# PDB2_1.net
KiCad netlist of a schematic drawn in EAGLE
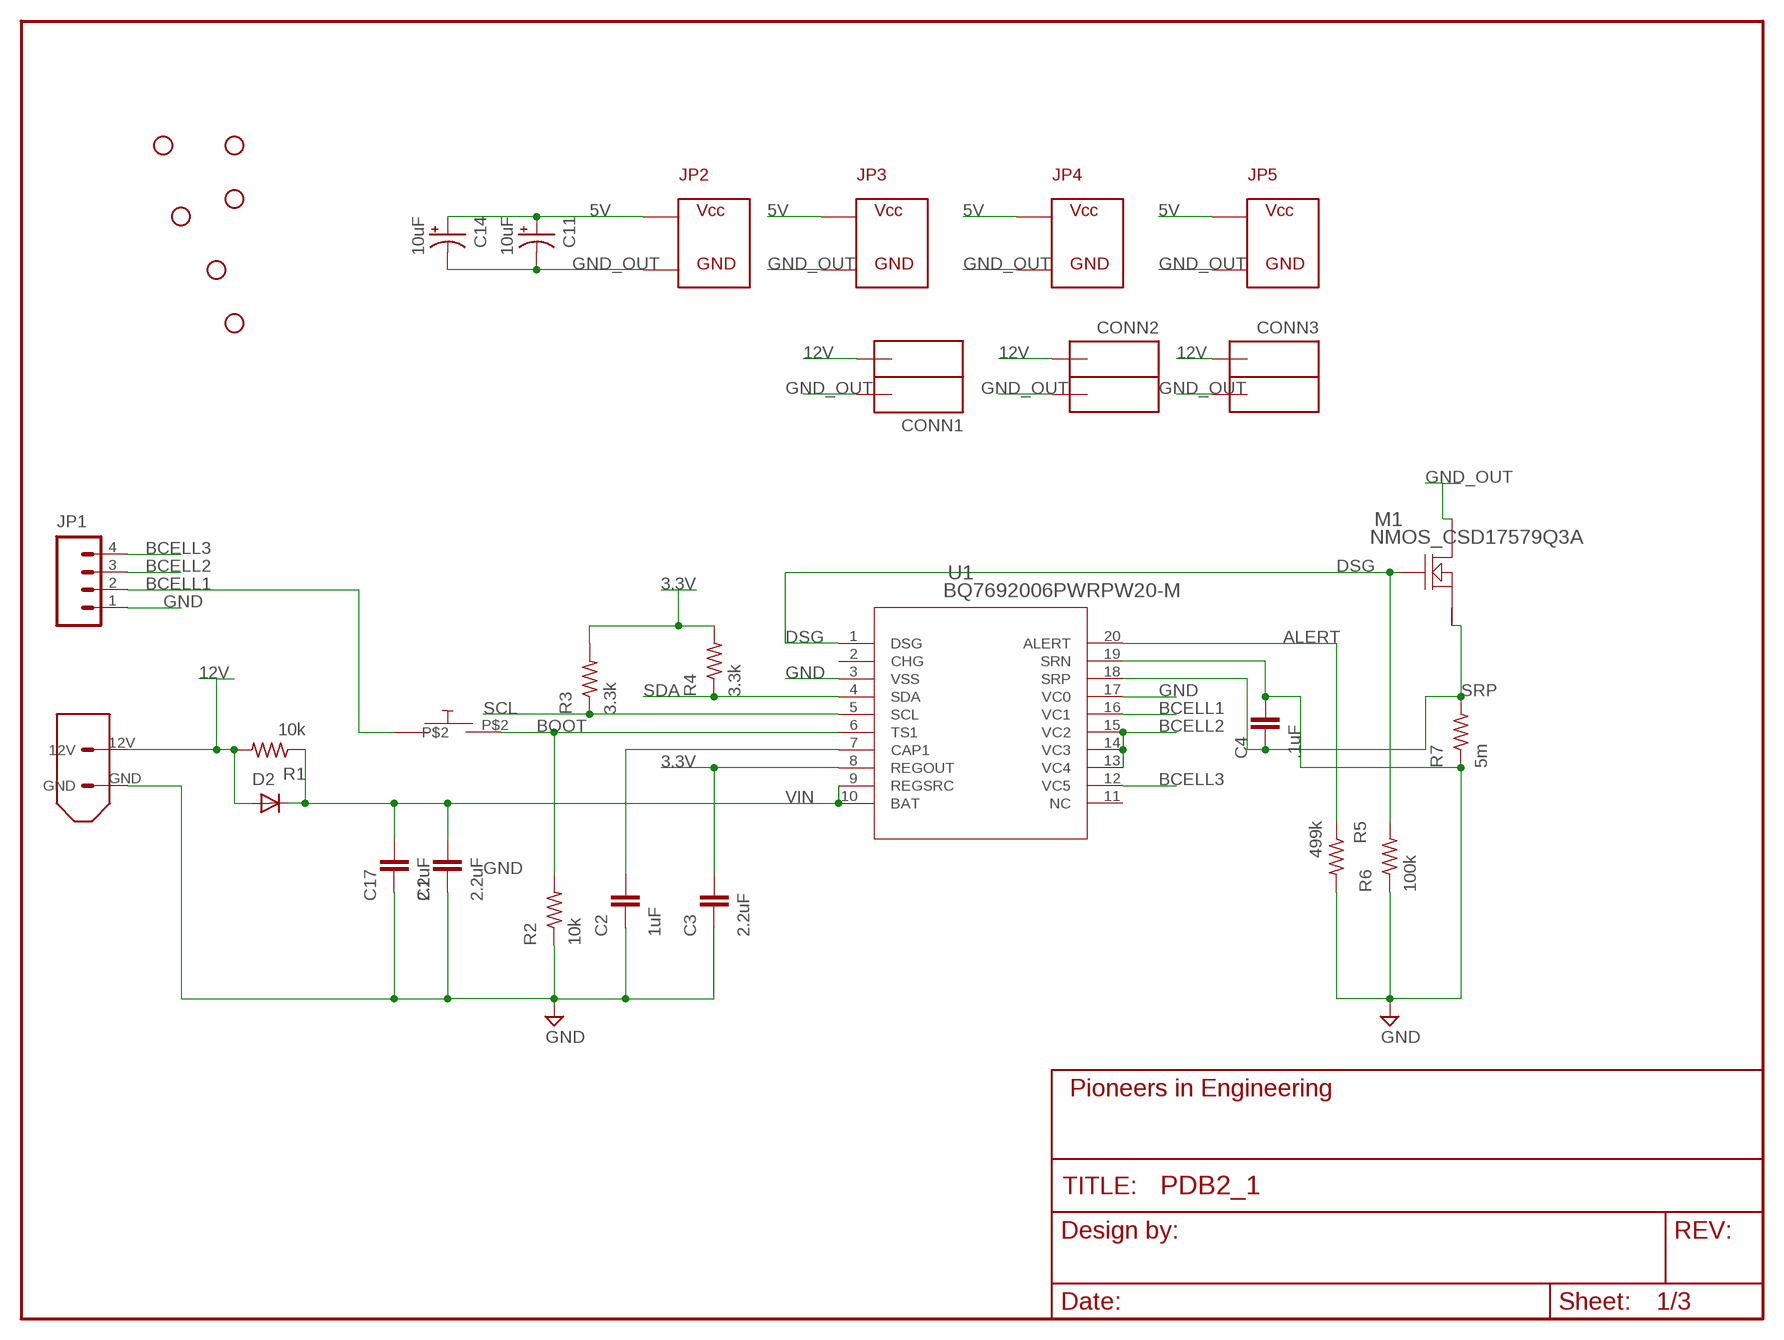
[diagram p0: schematic, sheet 1]
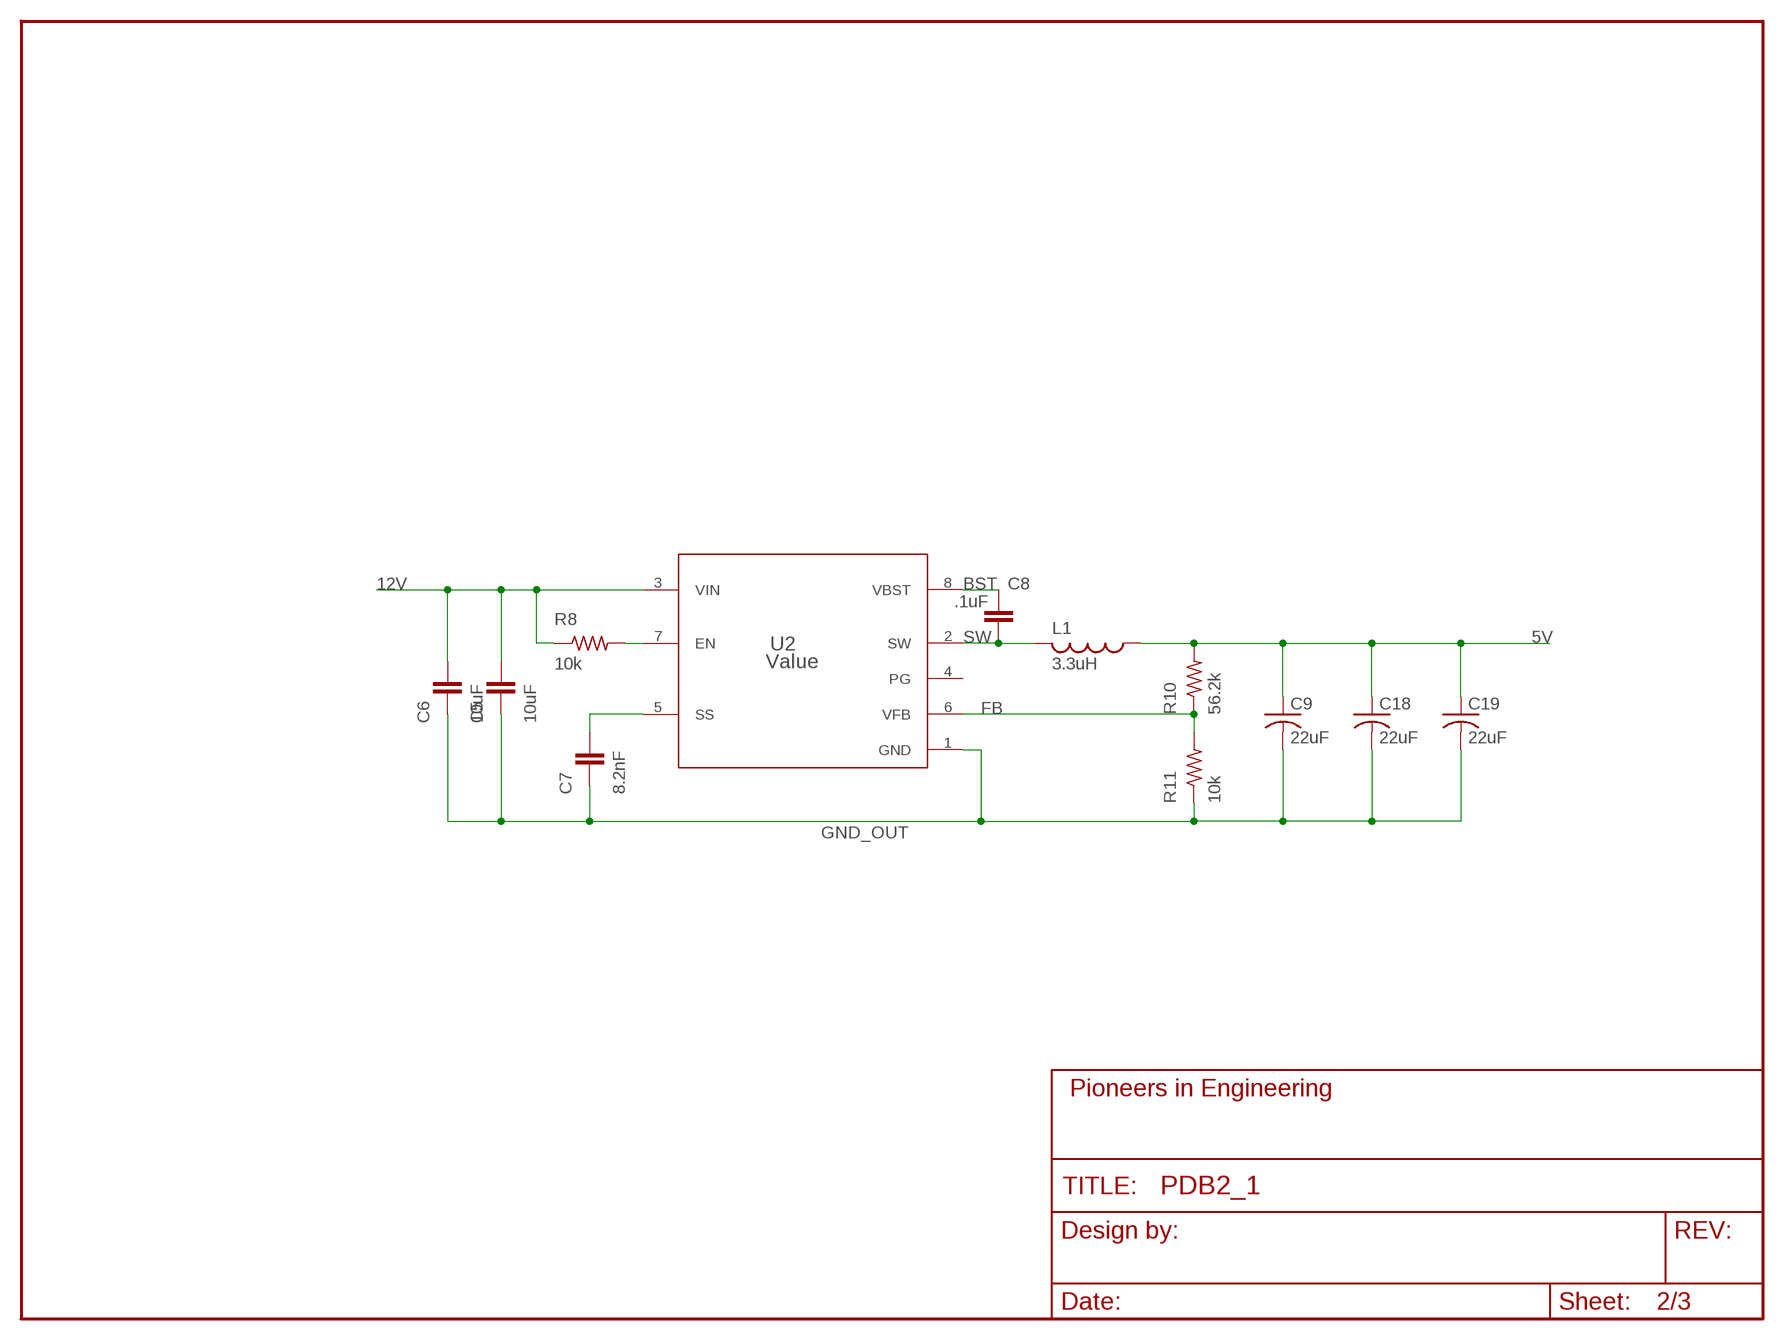
[diagram p1: schematic, sheet 2]
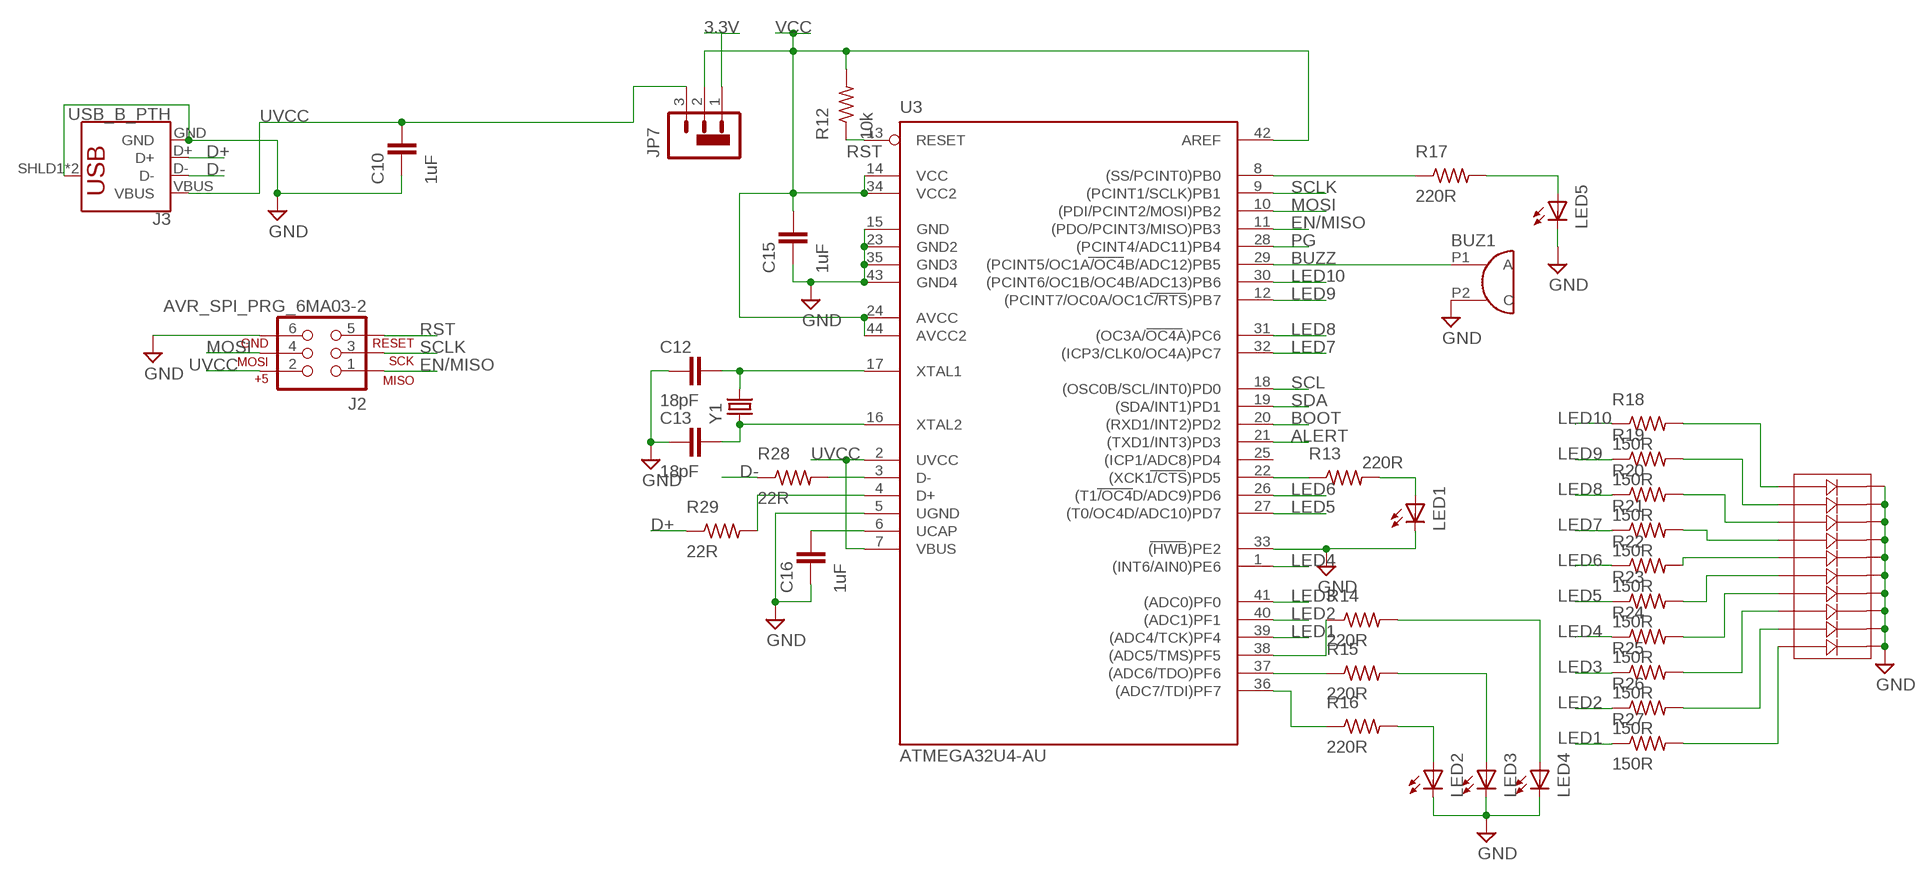
[diagram p2: schematic, sheet 3]

(export (version "E")
  (design (tool "Eeschema 10.0.6"))
  (components
    (comp (ref "C1")
      (value "2.2uF")
      (footprint "eagle-import:0603-CAP")
      (libsource (lib "eagle-import") (part "CAP0603-CAP"))
    )
    (comp (ref "C2")
      (value "1uF")
      (footprint "eagle-import:0603-CAP")
      (libsource (lib "eagle-import") (part "CAP0603-CAP"))
    )
    (comp (ref "C3")
      (value "2.2uF")
      (footprint "eagle-import:0603-CAP")
      (libsource (lib "eagle-import") (part "CAP0603-CAP"))
    )
    (comp (ref "C4")
      (value ".1uF")
      (footprint "eagle-import:0603-CAP")
      (libsource (lib "eagle-import") (part "CAP0603-CAP"))
    )
    (comp (ref "C11")
      (value "10uF")
      (footprint "eagle-import:.248_CAP_THRU")
      (libsource (lib "eagle-import") (part "CAP_POLRADIAL"))
    )
    (comp (ref "C14")
      (value "10uF")
      (footprint "eagle-import:.248_CAP_THRU")
      (libsource (lib "eagle-import") (part "CAP_POLRADIAL"))
    )
    (comp (ref "C17")
      (value "2.2uF")
      (footprint "eagle-import:0603-CAP")
      (libsource (lib "eagle-import") (part "CAP0603-CAP"))
    )
    (comp (ref "CONN1")
      (value "ANDERSONVERTICAL")
      (footprint "eagle-import:ANDERSON_VERTICAL")
      (libsource (lib "eagle-import") (part "ANDERSONVERTICAL"))
    )
    (comp (ref "CONN2")
      (value "ANDERSONVERTICAL")
      (footprint "eagle-import:ANDERSON_VERTICAL")
      (libsource (lib "eagle-import") (part "ANDERSONVERTICAL"))
    )
    (comp (ref "CONN3")
      (value "ANDERSONVERTICAL")
      (footprint "eagle-import:ANDERSON_VERTICAL")
      (libsource (lib "eagle-import") (part "ANDERSONVERTICAL"))
    )
    (comp (ref "D2")
      (value "D_MBR1020VL")
      (footprint "eagle-import:SOD-123FL")
      (fields (field (name "PART_NO") "MBR1020VL"))
      (libsource (lib "eagle-import") (part "D_MBR1020VL"))
    )
    (comp (ref "J1")
      (value "XT60CONNECTOR")
      (footprint "eagle-import:XT60CONNECTOR")
      (fields (field (name "PARTNUMBER") "PRT-10474 "))
      (libsource (lib "eagle-import") (part "XT60CONNECTOR"))
    )
    (comp (ref "JP1")
      (value "M041X04-MTA")
      (footprint "eagle-import:1X04-MTA")
      (libsource (lib "eagle-import") (part "M041X04-MTA"))
    )
    (comp (ref "JP2")
      (value "ATX")
      (footprint "eagle-import:ATX")
      (libsource (lib "eagle-import") (part "ATX"))
    )
    (comp (ref "JP3")
      (value "ATX")
      (footprint "eagle-import:ATX")
      (libsource (lib "eagle-import") (part "ATX"))
    )
    (comp (ref "JP4")
      (value "ATX")
      (footprint "eagle-import:ATX")
      (libsource (lib "eagle-import") (part "ATX"))
    )
    (comp (ref "JP5")
      (value "ATX")
      (footprint "eagle-import:ATX")
      (libsource (lib "eagle-import") (part "ATX"))
    )
    (comp (ref "M1")
      (value "NMOS_CSD17579Q3A")
      (footprint "eagle-import:DNH0008A")
      (fields
        (field (name "MANUFACTURER_PART_NUMBER") "CSD17579Q3A")
        (field (name "MANUFACTURER_PART_NUMBER_1") "CSD16401Q5")
      )
      (libsource (lib "eagle-import") (part "NMOS_CSD17579Q3A"))
    )
    (comp (ref "R1")
      (value "10k")
      (footprint "eagle-import:R0603")
      (fields (field (name "MANUFACTURER") "Rohm Semiconductor"))
      (libsource (lib "eagle-import") (part "R-US_R0603"))
    )
    (comp (ref "R2")
      (value "10k")
      (footprint "eagle-import:R0603")
      (fields (field (name "MANUFACTURER") "Rohm Semiconductor"))
      (libsource (lib "eagle-import") (part "R-US_R0603"))
    )
    (comp (ref "R3")
      (value "3.3k")
      (footprint "eagle-import:R0603")
      (fields (field (name "MANUFACTURER") "Rohm Semiconductor"))
      (libsource (lib "eagle-import") (part "R-US_R0603"))
    )
    (comp (ref "R4")
      (value "3.3k")
      (footprint "eagle-import:R0603")
      (fields (field (name "MANUFACTURER") "Rohm Semiconductor"))
      (libsource (lib "eagle-import") (part "R-US_R0603"))
    )
    (comp (ref "R5")
      (value "499k")
      (footprint "eagle-import:R0603")
      (fields (field (name "MANUFACTURER") "Rohm Semiconductor"))
      (libsource (lib "eagle-import") (part "R-US_R0603"))
    )
    (comp (ref "R6")
      (value "100k")
      (footprint "eagle-import:R0603")
      (fields (field (name "MANUFACTURER") "Rohm Semiconductor"))
      (libsource (lib "eagle-import") (part "R-US_R0603"))
    )
    (comp (ref "R7")
      (value "5m")
      (footprint "eagle-import:SMD_SHUNT")
      (fields (field (name "MANUFACTURER_PART_NO") "WSHM28185L000FEA"))
      (libsource (lib "eagle-import") (part "SHUNT_SMD"))
    )
    (comp (ref "STANDOFF1")
      (value "STAND-OFFTIGHT")
      (footprint "eagle-import:STAND-OFF-TIGHT")
      (libsource (lib "eagle-import") (part "STAND-OFFTIGHT"))
    )
    (comp (ref "STANDOFF2")
      (value "STAND-OFFTIGHT")
      (footprint "eagle-import:STAND-OFF-TIGHT")
      (libsource (lib "eagle-import") (part "STAND-OFFTIGHT"))
    )
    (comp (ref "STANDOFF3")
      (value "STAND-OFFTIGHT")
      (footprint "eagle-import:STAND-OFF-TIGHT")
      (libsource (lib "eagle-import") (part "STAND-OFFTIGHT"))
    )
    (comp (ref "STANDOFF4")
      (value "STAND-OFFTIGHT")
      (footprint "eagle-import:STAND-OFF-TIGHT")
      (libsource (lib "eagle-import") (part "STAND-OFFTIGHT"))
    )
    (comp (ref "STANDOFF5")
      (value "STAND-OFFTIGHT")
      (footprint "eagle-import:STAND-OFF-TIGHT")
      (libsource (lib "eagle-import") (part "STAND-OFFTIGHT"))
    )
    (comp (ref "STANDOFF7")
      (value "STAND-OFFTIGHT")
      (footprint "eagle-import:STAND-OFF-TIGHT")
      (libsource (lib "eagle-import") (part "STAND-OFFTIGHT"))
    )
    (comp (ref "SW1")
      (value "PUSH_BUTTON")
      (footprint "eagle-import:BUTTON_K12A")
      (libsource (lib "eagle-import") (part "PUSH_BUTTON"))
    )
    (comp (ref "U1")
      (value "BQ7692006PWRPW20-M")
      (footprint "eagle-import:PW20-M")
      (fields (field (name "MANUFACTURER_PART_NUMBER") "BQ7692006PWR"))
      (libsource (lib "eagle-import") (part "BQ7692006PWRPW20-M"))
    )
    (comp (ref "BUZ1")
      (value "BUZZER3.3VBUZZER")
      (footprint "eagle-import:BUZZER_3.3V")
      (libsource (lib "eagle-import") (part "BUZZER3.3VBUZZER"))
    )
    (comp (ref "C10")
      (value "1uF")
      (footprint "eagle-import:0603-CAP")
      (libsource (lib "eagle-import") (part "CAP0603-CAP"))
    )
    (comp (ref "C12")
      (value "18pF")
      (footprint "eagle-import:0603-CAP")
      (libsource (lib "eagle-import") (part "CAP0603-CAP"))
    )
    (comp (ref "C13")
      (value "18pF")
      (footprint "eagle-import:0603-CAP")
      (libsource (lib "eagle-import") (part "CAP0603-CAP"))
    )
    (comp (ref "C15")
      (value "1uF")
      (footprint "eagle-import:0603-CAP")
      (libsource (lib "eagle-import") (part "CAP0603-CAP"))
    )
    (comp (ref "C16")
      (value "1uF")
      (footprint "eagle-import:0603-CAP")
      (libsource (lib "eagle-import") (part "CAP0603-CAP"))
    )
    (comp (ref "J2")
      (value "AVR_SPI_PRG_6MA03-2")
      (footprint "eagle-import:MA03-2")
      (libsource (lib "eagle-import") (part "AVR_SPI_PRG_6MA03-2"))
    )
    (comp (ref "J3")
      (value "USB_B_PTH")
      (footprint "eagle-import:USB-B-PTH")
      (libsource (lib "eagle-import") (part "USB_B_PTH"))
    )
    (comp (ref "JP7")
      (value "JMP-OPTION")
      (footprint "eagle-import:1X03-JMP-OPTION")
      (libsource (lib "eagle-import") (part "JMP-OPTION"))
    )
    (comp (ref "LED1")
      (value "LED0805")
      (footprint "eagle-import:LED-0805")
      (libsource (lib "eagle-import") (part "LED0805"))
    )
    (comp (ref "LED2")
      (value "LED0805")
      (footprint "eagle-import:LED-0805")
      (libsource (lib "eagle-import") (part "LED0805"))
    )
    (comp (ref "LED3")
      (value "LED0805")
      (footprint "eagle-import:LED-0805")
      (libsource (lib "eagle-import") (part "LED0805"))
    )
    (comp (ref "LED4")
      (value "LED0805")
      (footprint "eagle-import:LED-0805")
      (libsource (lib "eagle-import") (part "LED0805"))
    )
    (comp (ref "LED5")
      (value "LED0805")
      (footprint "eagle-import:LED-0805")
      (libsource (lib "eagle-import") (part "LED0805"))
    )
    (comp (ref "LED6")
      (value "BAR_SEGMENT_DISPLAY")
      (footprint "eagle-import:BAR_SEGMENT_DISPLAY")
      (libsource (lib "eagle-import") (part "BAR_SEGMENT_DISPLAY"))
    )
    (comp (ref "R12")
      (value "10k")
      (footprint "eagle-import:R0603")
      (fields (field (name "MANUFACTURER") "Rohm Semiconductor"))
      (libsource (lib "eagle-import") (part "R-US_R0603"))
    )
    (comp (ref "R13")
      (value "220R")
      (footprint "eagle-import:R0603")
      (fields (field (name "MANUFACTURER") "Rohm Semiconductor"))
      (libsource (lib "eagle-import") (part "R-US_R0603"))
    )
    (comp (ref "R14")
      (value "220R")
      (footprint "eagle-import:R0603")
      (fields (field (name "MANUFACTURER") "Rohm Semiconductor"))
      (libsource (lib "eagle-import") (part "R-US_R0603"))
    )
    (comp (ref "R15")
      (value "220R")
      (footprint "eagle-import:R0603")
      (fields (field (name "MANUFACTURER") "Rohm Semiconductor"))
      (libsource (lib "eagle-import") (part "R-US_R0603"))
    )
    (comp (ref "R16")
      (value "220R")
      (footprint "eagle-import:R0603")
      (fields (field (name "MANUFACTURER") "Rohm Semiconductor"))
      (libsource (lib "eagle-import") (part "R-US_R0603"))
    )
    (comp (ref "R17")
      (value "220R")
      (footprint "eagle-import:R0603")
      (fields (field (name "MANUFACTURER") "Rohm Semiconductor"))
      (libsource (lib "eagle-import") (part "R-US_R0603"))
    )
    (comp (ref "R18")
      (value "150R")
      (footprint "eagle-import:R0603")
      (fields (field (name "MANUFACTURER") "Rohm Semiconductor"))
      (libsource (lib "eagle-import") (part "R-US_R0603"))
    )
    (comp (ref "R19")
      (value "150R")
      (footprint "eagle-import:R0603")
      (fields (field (name "MANUFACTURER") "Rohm Semiconductor"))
      (libsource (lib "eagle-import") (part "R-US_R0603"))
    )
    (comp (ref "R20")
      (value "150R")
      (footprint "eagle-import:R0603")
      (fields (field (name "MANUFACTURER") "Rohm Semiconductor"))
      (libsource (lib "eagle-import") (part "R-US_R0603"))
    )
    (comp (ref "R21")
      (value "150R")
      (footprint "eagle-import:R0603")
      (fields (field (name "MANUFACTURER") "Rohm Semiconductor"))
      (libsource (lib "eagle-import") (part "R-US_R0603"))
    )
    (comp (ref "R22")
      (value "150R")
      (footprint "eagle-import:R0603")
      (fields (field (name "MANUFACTURER") "Rohm Semiconductor"))
      (libsource (lib "eagle-import") (part "R-US_R0603"))
    )
    (comp (ref "R23")
      (value "150R")
      (footprint "eagle-import:R0603")
      (fields (field (name "MANUFACTURER") "Rohm Semiconductor"))
      (libsource (lib "eagle-import") (part "R-US_R0603"))
    )
    (comp (ref "R24")
      (value "150R")
      (footprint "eagle-import:R0603")
      (fields (field (name "MANUFACTURER") "Rohm Semiconductor"))
      (libsource (lib "eagle-import") (part "R-US_R0603"))
    )
    (comp (ref "R25")
      (value "150R")
      (footprint "eagle-import:R0603")
      (fields (field (name "MANUFACTURER") "Rohm Semiconductor"))
      (libsource (lib "eagle-import") (part "R-US_R0603"))
    )
    (comp (ref "R26")
      (value "150R")
      (footprint "eagle-import:R0603")
      (fields (field (name "MANUFACTURER") "Rohm Semiconductor"))
      (libsource (lib "eagle-import") (part "R-US_R0603"))
    )
    (comp (ref "R27")
      (value "150R")
      (footprint "eagle-import:R0603")
      (fields (field (name "MANUFACTURER") "Rohm Semiconductor"))
      (libsource (lib "eagle-import") (part "R-US_R0603"))
    )
    (comp (ref "R28")
      (value "22R")
      (footprint "eagle-import:R0603")
      (fields (field (name "MANUFACTURER") "Rohm Semiconductor"))
      (libsource (lib "eagle-import") (part "R-US_R0603"))
    )
    (comp (ref "R29")
      (value "22R")
      (footprint "eagle-import:R0603")
      (fields (field (name "MANUFACTURER") "Rohm Semiconductor"))
      (libsource (lib "eagle-import") (part "R-US_R0603"))
    )
    (comp (ref "U3")
      (value "ATMEGA32U4-AU")
      (footprint "eagle-import:TQFP44")
      (libsource (lib "eagle-import") (part "ATMEGA32U4-AU"))
    )
    (comp (ref "Y1")
      (value "CRYSTAL10.5X4.8")
      (footprint "eagle-import:CRYSTAL-SMD-10.5X4.8-2PIN")
      (fields (field (name "PART_NO") "ECS-160-20-3X-EN-TR"))
      (libsource (lib "eagle-import") (part "CRYSTAL10.5X4.8"))
    )
    (comp (ref "C5")
      (value "10uF")
      (footprint "eagle-import:0805")
      (libsource (lib "eagle-import") (part "CAP0805"))
    )
    (comp (ref "C6")
      (value "10uF")
      (footprint "eagle-import:0805")
      (libsource (lib "eagle-import") (part "CAP0805"))
    )
    (comp (ref "C7")
      (value "8.2nF")
      (footprint "eagle-import:0603-CAP")
      (libsource (lib "eagle-import") (part "CAP0603-CAP"))
    )
    (comp (ref "C8")
      (value ".1uF")
      (footprint "eagle-import:0603-CAP")
      (libsource (lib "eagle-import") (part "CAP0603-CAP"))
    )
    (comp (ref "C9")
      (value "22uF")
      (footprint "eagle-import:C0805")
      (libsource (lib "eagle-import") (part "C-USC0805"))
    )
    (comp (ref "C18")
      (value "22uF")
      (footprint "eagle-import:C0805")
      (libsource (lib "eagle-import") (part "C-USC0805"))
    )
    (comp (ref "C19")
      (value "22uF")
      (footprint "eagle-import:C0805")
      (libsource (lib "eagle-import") (part "C-USC0805"))
    )
    (comp (ref "L1")
      (value "3.3uH")
      (footprint "eagle-import:MWSA0402S")
      (libsource (lib "eagle-import") (part "MWSA0420S_INDUCTORMW"))
    )
    (comp (ref "R8")
      (value "10k")
      (footprint "eagle-import:R0603")
      (fields (field (name "MANUFACTURER") "Rohm Semiconductor"))
      (libsource (lib "eagle-import") (part "R-US_R0603"))
    )
    (comp (ref "R10")
      (value "56.2k")
      (footprint "eagle-import:R0603")
      (fields (field (name "MANUFACTURER") "Rohm Semiconductor"))
      (libsource (lib "eagle-import") (part "R-US_R0603"))
    )
    (comp (ref "R11")
      (value "10k")
      (footprint "eagle-import:R0603")
      (fields (field (name "MANUFACTURER") "Rohm Semiconductor"))
      (libsource (lib "eagle-import") (part "R-US_R0603"))
    )
    (comp (ref "U2")
      (value "Value")
      (footprint "eagle-import:DDF0008A_N")
      (fields
        (field (name "MANUFACTURER") "Texas Instruments")
        (field (name "MANUFACTURER_PART_NUMBER") "TPS563210ADDFR")
      )
      (libsource (lib "eagle-import") (part "TPS563210ADDFR"))
    )
  )
  (nets
    (net (code "1") (name "3.3V") (class "Default")
      (node (ref "C3") (pin "2") (pinfunction "2_2") (pintype "passive"))
      (node (ref "JP7") (pin "1") (pinfunction "1_1") (pintype "passive"))
      (node (ref "R3") (pin "2") (pinfunction "2_2") (pintype "passive"))
      (node (ref "R4") (pin "2") (pinfunction "2_2") (pintype "passive"))
      (node (ref "U1") (pin "8") (pinfunction "REGOUT_8") (pintype "power_in"))
    )
    (net (code "2") (name "5V") (class "Default")
      (node (ref "C11") (pin "PLUS") (pinfunction "+_PLUS") (pintype "passive"))
      (node (ref "C14") (pin "PLUS") (pinfunction "+_PLUS") (pintype "passive"))
      (node (ref "C18") (pin "1") (pinfunction "1_1") (pintype "passive"))
      (node (ref "C19") (pin "1") (pinfunction "1_1") (pintype "passive"))
      (node (ref "C9") (pin "1") (pinfunction "1_1") (pintype "passive"))
      (node (ref "JP2") (pin "P$1") (pinfunction "P$1_P$1") (pintype "power_in"))
      (node (ref "JP3") (pin "P$1") (pinfunction "P$1_P$1") (pintype "power_in"))
      (node (ref "JP4") (pin "P$1") (pinfunction "P$1_P$1") (pintype "power_in"))
      (node (ref "JP5") (pin "P$1") (pinfunction "P$1_P$1") (pintype "power_in"))
      (node (ref "L1") (pin "P$1") (pinfunction "1_P$1") (pintype "passive"))
      (node (ref "R10") (pin "2") (pinfunction "2_2") (pintype "passive"))
    )
    (net (code "3") (name "12V") (class "Default")
      (node (ref "C5") (pin "2") (pinfunction "2_2") (pintype "passive"))
      (node (ref "C6") (pin "2") (pinfunction "2_2") (pintype "passive"))
      (node (ref "CONN1") (pin "PIN1") (pinfunction "OUTB_PIN1") (pintype "bidirectional"))
      (node (ref "CONN2") (pin "PIN2") (pinfunction "OUTA_PIN2") (pintype "bidirectional"))
      (node (ref "CONN3") (pin "PIN2") (pinfunction "OUTA_PIN2") (pintype "bidirectional"))
      (node (ref "D2") (pin "P$2") (pinfunction "A_P$2") (pintype "passive"))
      (node (ref "J1") (pin "12V") (pinfunction "12V_12V") (pintype "bidirectional"))
      (node (ref "R1") (pin "2") (pinfunction "2_2") (pintype "passive"))
      (node (ref "R8") (pin "1") (pinfunction "1_1") (pintype "passive"))
      (node (ref "U2") (pin "3") (pinfunction "VIN_3") (pintype "power_in"))
    )
    (net (code "4") (name "ALERT") (class "Default")
      (node (ref "R5") (pin "1") (pinfunction "1_1") (pintype "passive"))
      (node (ref "U1") (pin "20") (pinfunction "ALERT_20") (pintype "bidirectional"))
      (node (ref "U3") (pin "21") (pinfunction "(TXD1/INT3)PD3_21") (pintype "bidirectional"))
    )
    (net (code "5") (name "BCELL1") (class "Default")
      (node (ref "JP1") (pin "2") (pinfunction "2_2") (pintype "passive"))
      (node (ref "SW1") (pin "P$1") (pinfunction "P$1_P$1") (pintype "bidirectional"))
      (node (ref "U1") (pin "16") (pinfunction "VC1_16") (pintype "input"))
    )
    (net (code "6") (name "BCELL2") (class "Default")
      (node (ref "JP1") (pin "3") (pinfunction "3_3") (pintype "passive"))
      (node (ref "U1") (pin "13") (pinfunction "VC4_13") (pintype "input"))
      (node (ref "U1") (pin "14") (pinfunction "VC3_14") (pintype "input"))
      (node (ref "U1") (pin "15") (pinfunction "VC2_15") (pintype "input"))
    )
    (net (code "7") (name "BCELL3") (class "Default")
      (node (ref "JP1") (pin "4") (pinfunction "4_4") (pintype "passive"))
      (node (ref "U1") (pin "12") (pinfunction "VC5_12") (pintype "input"))
    )
    (net (code "8") (name "BOOT") (class "Default")
      (node (ref "R2") (pin "2") (pinfunction "2_2") (pintype "passive"))
      (node (ref "SW1") (pin "P$2") (pinfunction "P$2_P$2") (pintype "bidirectional"))
      (node (ref "U1") (pin "6") (pinfunction "TS1_6") (pintype "input"))
      (node (ref "U3") (pin "20") (pinfunction "(RXD1/INT2)PD2_20") (pintype "bidirectional"))
    )
    (net (code "9") (name "BST") (class "Default")
      (node (ref "C8") (pin "1") (pinfunction "1_1") (pintype "passive"))
      (node (ref "U2") (pin "8") (pinfunction "VBST_8") (pintype "power_in"))
    )
    (net (code "10") (name "BUZZ") (class "Default")
      (node (ref "BUZ1") (pin "P1") (pinfunction "A_P1") (pintype "bidirectional"))
      (node (ref "U3") (pin "29") (pinfunction "(PCINT5/OC1A/OC4B/ADC12)PB5_29") (pintype "bidirectional"))
    )
    (net (code "11") (name "D+") (class "Default")
      (node (ref "J3") (pin "D+") (pinfunction "D+_D+") (pintype "bidirectional"))
      (node (ref "R29") (pin "1") (pinfunction "1_1") (pintype "passive"))
    )
    (net (code "12") (name "D-") (class "Default")
      (node (ref "J3") (pin "D-") (pinfunction "D-_D-") (pintype "bidirectional"))
      (node (ref "R28") (pin "1") (pinfunction "1_1") (pintype "passive"))
    )
    (net (code "13") (name "DSG") (class "Default")
      (node (ref "M1") (pin "4") (pinfunction "GATE_4") (pintype "passive"))
      (node (ref "R6") (pin "2") (pinfunction "2_2") (pintype "passive"))
      (node (ref "U1") (pin "1") (pinfunction "DSG_1") (pintype "output"))
    )
    (net (code "14") (name "EN{slash}MISO") (class "Default")
      (node (ref "J2") (pin "1") (pinfunction "1_1") (pintype "passive"))
      (node (ref "U3") (pin "11") (pinfunction "(PDO/PCINT3/MISO)PB3_11") (pintype "bidirectional"))
    )
    (net (code "15") (name "FB") (class "Default")
      (node (ref "R10") (pin "1") (pinfunction "1_1") (pintype "passive"))
      (node (ref "R11") (pin "2") (pinfunction "2_2") (pintype "passive"))
      (node (ref "U2") (pin "6") (pinfunction "VFB_6") (pintype "input"))
    )
    (net (code "16") (name "GND") (class "Default")
      (node (ref "BUZ1") (pin "P2") (pinfunction "C_P2") (pintype "bidirectional"))
      (node (ref "C1") (pin "1") (pinfunction "1_1") (pintype "passive"))
      (node (ref "C10") (pin "1") (pinfunction "1_1") (pintype "passive"))
      (node (ref "C12") (pin "1") (pinfunction "1_1") (pintype "passive"))
      (node (ref "C13") (pin "1") (pinfunction "1_1") (pintype "passive"))
      (node (ref "C15") (pin "1") (pinfunction "1_1") (pintype "passive"))
      (node (ref "C16") (pin "1") (pinfunction "1_1") (pintype "passive"))
      (node (ref "C17") (pin "1") (pinfunction "1_1") (pintype "passive"))
      (node (ref "C2") (pin "1") (pinfunction "1_1") (pintype "passive"))
      (node (ref "C3") (pin "1") (pinfunction "1_1") (pintype "passive"))
      (node (ref "C4") (pin "2") (pinfunction "2_2") (pintype "passive"))
      (node (ref "J1") (pin "GND") (pinfunction "GND_GND") (pintype "bidirectional"))
      (node (ref "J2") (pin "6") (pinfunction "6_6") (pintype "passive"))
      (node (ref "J3") (pin "GND") (pinfunction "GND_GND") (pintype "power_in"))
      (node (ref "J3") (pin "SHLD1") (pinfunction "SHIELD_SHLD1") (pintype "bidirectional"))
      (node (ref "J3") (pin "SHLD2") (pinfunction "SHIELD_SHLD2") (pintype "bidirectional"))
      (node (ref "JP1") (pin "1") (pinfunction "1_1") (pintype "passive"))
      (node (ref "LED1") (pin "C") (pinfunction "C_C") (pintype "passive"))
      (node (ref "LED2") (pin "C") (pinfunction "C_C") (pintype "passive"))
      (node (ref "LED3") (pin "C") (pinfunction "C_C") (pintype "passive"))
      (node (ref "LED4") (pin "C") (pinfunction "C_C") (pintype "passive"))
      (node (ref "LED5") (pin "C") (pinfunction "C_C") (pintype "passive"))
      (node (ref "LED6") (pin "BAR_DISPLAY10") (pinfunction "P11_BAR_DISPLAY10") (pintype "bidirectional"))
      (node (ref "LED6") (pin "BAR_DISPLAY11") (pinfunction "P12_BAR_DISPLAY11") (pintype "bidirectional"))
      (node (ref "LED6") (pin "BAR_DISPLAY12") (pinfunction "P13_BAR_DISPLAY12") (pintype "bidirectional"))
      (node (ref "LED6") (pin "BAR_DISPLAY13") (pinfunction "P14_BAR_DISPLAY13") (pintype "bidirectional"))
      (node (ref "LED6") (pin "BAR_DISPLAY14") (pinfunction "P15_BAR_DISPLAY14") (pintype "bidirectional"))
      (node (ref "LED6") (pin "BAR_DISPLAY15") (pinfunction "P16_BAR_DISPLAY15") (pintype "bidirectional"))
      (node (ref "LED6") (pin "BAR_DISPLAY16") (pinfunction "P17_BAR_DISPLAY16") (pintype "bidirectional"))
      (node (ref "LED6") (pin "BAR_DISPLAY17") (pinfunction "P18_BAR_DISPLAY17") (pintype "bidirectional"))
      (node (ref "LED6") (pin "BAR_DISPLAY18") (pinfunction "P19_BAR_DISPLAY18") (pintype "bidirectional"))
      (node (ref "LED6") (pin "BAR_DISPLAY19") (pinfunction "P20_BAR_DISPLAY19") (pintype "bidirectional"))
      (node (ref "R2") (pin "1") (pinfunction "1_1") (pintype "passive"))
      (node (ref "R5") (pin "2") (pinfunction "2_2") (pintype "passive"))
      (node (ref "R6") (pin "1") (pinfunction "1_1") (pintype "passive"))
      (node (ref "R7") (pin "P$1") (pinfunction "1_P$1") (pintype "passive"))
      (node (ref "U1") (pin "17") (pinfunction "VC0_17") (pintype "input"))
      (node (ref "U1") (pin "19") (pinfunction "SRN_19") (pintype "input"))
      (node (ref "U1") (pin "3") (pinfunction "VSS_3") (pintype "power_in"))
      (node (ref "U3") (pin "15") (pinfunction "GND_15") (pintype "bidirectional"))
      (node (ref "U3") (pin "23") (pinfunction "GND2_23") (pintype "bidirectional"))
      (node (ref "U3") (pin "33") (pinfunction "(HWB)PE2_33") (pintype "bidirectional"))
      (node (ref "U3") (pin "35") (pinfunction "GND3_35") (pintype "bidirectional"))
      (node (ref "U3") (pin "43") (pinfunction "GND4_43") (pintype "bidirectional"))
      (node (ref "U3") (pin "5") (pinfunction "UGND_5") (pintype "bidirectional"))
    )
    (net (code "17") (name "GND_OUT") (class "Default")
      (node (ref "C11") (pin "MINUS") (pinfunction "-_MINUS") (pintype "passive"))
      (node (ref "C14") (pin "MINUS") (pinfunction "-_MINUS") (pintype "passive"))
      (node (ref "C18") (pin "2") (pinfunction "2_2") (pintype "passive"))
      (node (ref "C19") (pin "2") (pinfunction "2_2") (pintype "passive"))
      (node (ref "C5") (pin "1") (pinfunction "1_1") (pintype "passive"))
      (node (ref "C6") (pin "1") (pinfunction "1_1") (pintype "passive"))
      (node (ref "C7") (pin "1") (pinfunction "1_1") (pintype "passive"))
      (node (ref "C9") (pin "2") (pinfunction "2_2") (pintype "passive"))
      (node (ref "CONN1") (pin "PIN2") (pinfunction "OUTA_PIN2") (pintype "bidirectional"))
      (node (ref "CONN2") (pin "PIN1") (pinfunction "OUTB_PIN1") (pintype "bidirectional"))
      (node (ref "CONN3") (pin "PIN1") (pinfunction "OUTB_PIN1") (pintype "bidirectional"))
      (node (ref "JP2") (pin "P$2") (pinfunction "P$2_P$2") (pintype "power_in"))
      (node (ref "JP3") (pin "P$2") (pinfunction "P$2_P$2") (pintype "power_in"))
      (node (ref "JP4") (pin "P$2") (pinfunction "P$2_P$2") (pintype "power_in"))
      (node (ref "JP5") (pin "P$2") (pinfunction "P$2_P$2") (pintype "power_in"))
      (node (ref "M1") (pin "5") (pinfunction "DRAIN_2_5") (pintype "passive"))
      (node (ref "M1") (pin "6") (pinfunction "DRAIN_2_6") (pintype "passive"))
      (node (ref "M1") (pin "7") (pinfunction "DRAIN_2_7") (pintype "passive"))
      (node (ref "M1") (pin "8") (pinfunction "DRAIN_2_8") (pintype "passive"))
      (node (ref "M1") (pin "9") (pinfunction "DRAIN_2_9") (pintype "passive"))
      (node (ref "R11") (pin "1") (pinfunction "1_1") (pintype "passive"))
      (node (ref "U2") (pin "1") (pinfunction "GND_1") (pintype "power_in"))
    )
    (net (code "18") (name "LED1") (class "Default")
      (node (ref "R27") (pin "1") (pinfunction "1_1") (pintype "passive"))
      (node (ref "U3") (pin "39") (pinfunction "(ADC4/TCK)PF4_39") (pintype "bidirectional"))
    )
    (net (code "19") (name "LED2") (class "Default")
      (node (ref "R26") (pin "1") (pinfunction "1_1") (pintype "passive"))
      (node (ref "U3") (pin "40") (pinfunction "(ADC1)PF1_40") (pintype "bidirectional"))
    )
    (net (code "20") (name "LED3") (class "Default")
      (node (ref "R25") (pin "1") (pinfunction "1_1") (pintype "passive"))
      (node (ref "U3") (pin "41") (pinfunction "(ADC0)PF0_41") (pintype "bidirectional"))
    )
    (net (code "21") (name "LED4") (class "Default")
      (node (ref "R24") (pin "1") (pinfunction "1_1") (pintype "passive"))
      (node (ref "U3") (pin "1") (pinfunction "(INT6/AIN0)PE6_1") (pintype "bidirectional"))
    )
    (net (code "22") (name "LED5") (class "Default")
      (node (ref "R23") (pin "1") (pinfunction "1_1") (pintype "passive"))
      (node (ref "U3") (pin "27") (pinfunction "(T0/OC4D/ADC10)PD7_27") (pintype "bidirectional"))
    )
    (net (code "23") (name "LED6") (class "Default")
      (node (ref "R22") (pin "1") (pinfunction "1_1") (pintype "passive"))
      (node (ref "U3") (pin "26") (pinfunction "(T1/OC4D/ADC9)PD6_26") (pintype "bidirectional"))
    )
    (net (code "24") (name "LED7") (class "Default")
      (node (ref "R21") (pin "1") (pinfunction "1_1") (pintype "passive"))
      (node (ref "U3") (pin "32") (pinfunction "(ICP3/CLK0/OC4A)PC7_32") (pintype "bidirectional"))
    )
    (net (code "25") (name "LED8") (class "Default")
      (node (ref "R20") (pin "1") (pinfunction "1_1") (pintype "passive"))
      (node (ref "U3") (pin "31") (pinfunction "(OC3A/OC4A)PC6_31") (pintype "bidirectional"))
    )
    (net (code "26") (name "LED9") (class "Default")
      (node (ref "R19") (pin "1") (pinfunction "1_1") (pintype "passive"))
      (node (ref "U3") (pin "12") (pinfunction "(PCINT7/OC0A/OC1C/RTS)PB7_12") (pintype "bidirectional"))
    )
    (net (code "27") (name "LED10") (class "Default")
      (node (ref "R18") (pin "1") (pinfunction "1_1") (pintype "passive"))
      (node (ref "U3") (pin "30") (pinfunction "(PCINT6/OC1B/OC4B/ADC13)PB6_30") (pintype "bidirectional"))
    )
    (net (code "28") (name "MOSI") (class "Default")
      (node (ref "J2") (pin "4") (pinfunction "4_4") (pintype "passive"))
      (node (ref "U3") (pin "10") (pinfunction "(PDI/PCINT2/MOSI)PB2_10") (pintype "bidirectional"))
    )
    (net (code "29") (name "Net-(LED1-PadA)") (class "Default")
      (node (ref "LED1") (pin "A") (pinfunction "A_A") (pintype "passive"))
      (node (ref "R13") (pin "2") (pinfunction "2_2") (pintype "passive"))
    )
    (net (code "30") (name "Net-(LED2-PadA)") (class "Default")
      (node (ref "LED2") (pin "A") (pinfunction "A_A") (pintype "passive"))
      (node (ref "R16") (pin "2") (pinfunction "2_2") (pintype "passive"))
    )
    (net (code "31") (name "Net-(LED3-PadA)") (class "Default")
      (node (ref "LED3") (pin "A") (pinfunction "A_A") (pintype "passive"))
      (node (ref "R15") (pin "2") (pinfunction "2_2") (pintype "passive"))
    )
    (net (code "32") (name "Net-(LED4-PadA)") (class "Default")
      (node (ref "LED4") (pin "A") (pinfunction "A_A") (pintype "passive"))
      (node (ref "R14") (pin "2") (pinfunction "2_2") (pintype "passive"))
    )
    (net (code "33") (name "Net-(LED5-PadA)") (class "Default")
      (node (ref "LED5") (pin "A") (pinfunction "A_A") (pintype "passive"))
      (node (ref "R17") (pin "2") (pinfunction "2_2") (pintype "passive"))
    )
    (net (code "34") (name "Net-(LED6-P1)") (class "Default")
      (node (ref "LED6") (pin "BAR_DISPLAY0") (pinfunction "P1_BAR_DISPLAY0") (pintype "bidirectional"))
      (node (ref "R18") (pin "2") (pinfunction "2_2") (pintype "passive"))
    )
    (net (code "35") (name "Net-(LED6-P2)") (class "Default")
      (node (ref "LED6") (pin "BAR_DISPLAY1") (pinfunction "P2_BAR_DISPLAY1") (pintype "bidirectional"))
      (node (ref "R19") (pin "2") (pinfunction "2_2") (pintype "passive"))
    )
    (net (code "36") (name "Net-(LED6-P3)") (class "Default")
      (node (ref "LED6") (pin "BAR_DISPLAY2") (pinfunction "P3_BAR_DISPLAY2") (pintype "bidirectional"))
      (node (ref "R20") (pin "2") (pinfunction "2_2") (pintype "passive"))
    )
    (net (code "37") (name "Net-(LED6-P4)") (class "Default")
      (node (ref "LED6") (pin "BAR_DISPLAY3") (pinfunction "P4_BAR_DISPLAY3") (pintype "bidirectional"))
      (node (ref "R21") (pin "2") (pinfunction "2_2") (pintype "passive"))
    )
    (net (code "38") (name "Net-(LED6-P5)") (class "Default")
      (node (ref "LED6") (pin "BAR_DISPLAY4") (pinfunction "P5_BAR_DISPLAY4") (pintype "bidirectional"))
      (node (ref "R22") (pin "2") (pinfunction "2_2") (pintype "passive"))
    )
    (net (code "39") (name "Net-(LED6-P6)") (class "Default")
      (node (ref "LED6") (pin "BAR_DISPLAY5") (pinfunction "P6_BAR_DISPLAY5") (pintype "bidirectional"))
      (node (ref "R23") (pin "2") (pinfunction "2_2") (pintype "passive"))
    )
    (net (code "40") (name "Net-(LED6-P7)") (class "Default")
      (node (ref "LED6") (pin "BAR_DISPLAY6") (pinfunction "P7_BAR_DISPLAY6") (pintype "bidirectional"))
      (node (ref "R24") (pin "2") (pinfunction "2_2") (pintype "passive"))
    )
    (net (code "41") (name "Net-(LED6-P8)") (class "Default")
      (node (ref "LED6") (pin "BAR_DISPLAY7") (pinfunction "P8_BAR_DISPLAY7") (pintype "bidirectional"))
      (node (ref "R25") (pin "2") (pinfunction "2_2") (pintype "passive"))
    )
    (net (code "42") (name "Net-(LED6-P9)") (class "Default")
      (node (ref "LED6") (pin "BAR_DISPLAY8") (pinfunction "P9_BAR_DISPLAY8") (pintype "bidirectional"))
      (node (ref "R26") (pin "2") (pinfunction "2_2") (pintype "passive"))
    )
    (net (code "43") (name "Net-(LED6-P10)") (class "Default")
      (node (ref "LED6") (pin "BAR_DISPLAY9") (pinfunction "P10_BAR_DISPLAY9") (pintype "bidirectional"))
      (node (ref "R27") (pin "2") (pinfunction "2_2") (pintype "passive"))
    )
    (net (code "44") (name "Net-(U1-CAP1)") (class "Default")
      (node (ref "C2") (pin "2") (pinfunction "2_2") (pintype "passive"))
      (node (ref "U1") (pin "7") (pinfunction "CAP1_7") (pintype "output"))
    )
    (net (code "45") (name "Net-(U2-EN)") (class "Default")
      (node (ref "R8") (pin "2") (pinfunction "2_2") (pintype "passive"))
      (node (ref "U2") (pin "7") (pinfunction "EN_7") (pintype "input"))
    )
    (net (code "46") (name "Net-(U2-SS)") (class "Default")
      (node (ref "C7") (pin "2") (pinfunction "2_2") (pintype "passive"))
      (node (ref "U2") (pin "5") (pinfunction "SS_5") (pintype "input"))
    )
    (net (code "47") (name "Net-(U3-(ADC5{slash}TMS)PF5)") (class "Default")
      (node (ref "R14") (pin "1") (pinfunction "1_1") (pintype "passive"))
      (node (ref "U3") (pin "38") (pinfunction "(ADC5/TMS)PF5_38") (pintype "bidirectional"))
    )
    (net (code "48") (name "Net-(U3-(ADC6{slash}TDO)PF6)") (class "Default")
      (node (ref "R15") (pin "1") (pinfunction "1_1") (pintype "passive"))
      (node (ref "U3") (pin "37") (pinfunction "(ADC6/TDO)PF6_37") (pintype "bidirectional"))
    )
    (net (code "49") (name "Net-(U3-(ADC7{slash}TDI)PF7)") (class "Default")
      (node (ref "R16") (pin "1") (pinfunction "1_1") (pintype "passive"))
      (node (ref "U3") (pin "36") (pinfunction "(ADC7/TDI)PF7_36") (pintype "bidirectional"))
    )
    (net (code "50") (name "Net-(U3-(SS{slash}PCINT0)PB0)") (class "Default")
      (node (ref "R17") (pin "1") (pinfunction "1_1") (pintype "passive"))
      (node (ref "U3") (pin "8") (pinfunction "(SS/PCINT0)PB0_8") (pintype "bidirectional"))
    )
    (net (code "51") (name "Net-(U3-(XCK1{slash}CTS)PD5)") (class "Default")
      (node (ref "R13") (pin "1") (pinfunction "1_1") (pintype "passive"))
      (node (ref "U3") (pin "22") (pinfunction "(XCK1/CTS)PD5_22") (pintype "bidirectional"))
    )
    (net (code "52") (name "Net-(U3-D+)") (class "Default")
      (node (ref "R29") (pin "2") (pinfunction "2_2") (pintype "passive"))
      (node (ref "U3") (pin "4") (pinfunction "D+_4") (pintype "bidirectional"))
    )
    (net (code "53") (name "Net-(U3-D-)") (class "Default")
      (node (ref "R28") (pin "2") (pinfunction "2_2") (pintype "passive"))
      (node (ref "U3") (pin "3") (pinfunction "D-_3") (pintype "bidirectional"))
    )
    (net (code "54") (name "Net-(U3-UCAP)") (class "Default")
      (node (ref "C16") (pin "2") (pinfunction "2_2") (pintype "passive"))
      (node (ref "U3") (pin "6") (pinfunction "UCAP_6") (pintype "bidirectional"))
    )
    (net (code "55") (name "Net-(U3-XTAL1)") (class "Default")
      (node (ref "C12") (pin "2") (pinfunction "2_2") (pintype "passive"))
      (node (ref "U3") (pin "17") (pinfunction "XTAL1_17") (pintype "bidirectional"))
      (node (ref "Y1") (pin "P$2") (pinfunction "2_P$2") (pintype "passive"))
    )
    (net (code "56") (name "Net-(U3-XTAL2)") (class "Default")
      (node (ref "C13") (pin "2") (pinfunction "2_2") (pintype "passive"))
      (node (ref "U3") (pin "16") (pinfunction "XTAL2_16") (pintype "bidirectional"))
      (node (ref "Y1") (pin "P$1") (pinfunction "1_P$1") (pintype "passive"))
    )
    (net (code "57") (name "PG") (class "Default")
      (node (ref "U3") (pin "28") (pinfunction "(PCINT4/ADC11)PB4_28") (pintype "bidirectional"))
    )
    (net (code "58") (name "RST") (class "Default")
      (node (ref "J2") (pin "5") (pinfunction "5_5") (pintype "passive"))
      (node (ref "R12") (pin "1") (pinfunction "1_1") (pintype "passive"))
      (node (ref "U3") (pin "13") (pinfunction "RESET_13") (pintype "bidirectional"))
    )
    (net (code "59") (name "SCL") (class "Default")
      (node (ref "R3") (pin "1") (pinfunction "1_1") (pintype "passive"))
      (node (ref "U1") (pin "5") (pinfunction "SCL_5") (pintype "input"))
      (node (ref "U3") (pin "18") (pinfunction "(OSC0B/SCL/INT0)PD0_18") (pintype "bidirectional"))
    )
    (net (code "60") (name "SCLK") (class "Default")
      (node (ref "J2") (pin "3") (pinfunction "3_3") (pintype "passive"))
      (node (ref "U3") (pin "9") (pinfunction "(PCINT1/SCLK)PB1_9") (pintype "bidirectional"))
    )
    (net (code "61") (name "SDA") (class "Default")
      (node (ref "R4") (pin "1") (pinfunction "1_1") (pintype "passive"))
      (node (ref "U1") (pin "4") (pinfunction "SDA_4") (pintype "bidirectional"))
      (node (ref "U3") (pin "19") (pinfunction "(SDA/INT1)PD1_19") (pintype "bidirectional"))
    )
    (net (code "62") (name "SRP") (class "Default")
      (node (ref "C4") (pin "1") (pinfunction "1_1") (pintype "passive"))
      (node (ref "M1") (pin "1") (pinfunction "SOURCE_2_1") (pintype "passive"))
      (node (ref "M1") (pin "2") (pinfunction "SOURCE_2_2") (pintype "passive"))
      (node (ref "M1") (pin "3") (pinfunction "SOURCE_2_3") (pintype "passive"))
      (node (ref "R7") (pin "P$2") (pinfunction "2_P$2") (pintype "passive"))
      (node (ref "U1") (pin "18") (pinfunction "SRP_18") (pintype "input"))
    )
    (net (code "63") (name "SW") (class "Default")
      (node (ref "C8") (pin "2") (pinfunction "2_2") (pintype "passive"))
      (node (ref "L1") (pin "P$2") (pinfunction "2_P$2") (pintype "passive"))
      (node (ref "U2") (pin "2") (pinfunction "SW_2") (pintype "power_in"))
    )
    (net (code "64") (name "UVCC") (class "Default")
      (node (ref "C10") (pin "2") (pinfunction "2_2") (pintype "passive"))
      (node (ref "J2") (pin "2") (pinfunction "2_2") (pintype "passive"))
      (node (ref "J3") (pin "VBUS") (pinfunction "VBUS_VBUS") (pintype "power_in"))
      (node (ref "JP7") (pin "3") (pinfunction "3_3") (pintype "passive"))
      (node (ref "U3") (pin "2") (pinfunction "UVCC_2") (pintype "bidirectional"))
      (node (ref "U3") (pin "7") (pinfunction "VBUS_7") (pintype "bidirectional"))
    )
    (net (code "65") (name "VCC") (class "Default")
      (node (ref "C15") (pin "2") (pinfunction "2_2") (pintype "passive"))
      (node (ref "JP7") (pin "2") (pinfunction "COMMON_2") (pintype "passive"))
      (node (ref "R12") (pin "2") (pinfunction "2_2") (pintype "passive"))
      (node (ref "U3") (pin "14") (pinfunction "VCC_14") (pintype "bidirectional"))
      (node (ref "U3") (pin "24") (pinfunction "AVCC_24") (pintype "bidirectional"))
      (node (ref "U3") (pin "34") (pinfunction "VCC2_34") (pintype "bidirectional"))
      (node (ref "U3") (pin "42") (pinfunction "AREF_42") (pintype "bidirectional"))
      (node (ref "U3") (pin "44") (pinfunction "AVCC2_44") (pintype "bidirectional"))
    )
    (net (code "66") (name "VIN") (class "Default")
      (node (ref "C1") (pin "2") (pinfunction "2_2") (pintype "passive"))
      (node (ref "C17") (pin "2") (pinfunction "2_2") (pintype "passive"))
      (node (ref "D2") (pin "P$1") (pinfunction "C_P$1") (pintype "passive"))
      (node (ref "R1") (pin "1") (pinfunction "1_1") (pintype "passive"))
      (node (ref "U1") (pin "10") (pinfunction "BAT_10") (pintype "power_in"))
      (node (ref "U1") (pin "9") (pinfunction "REGSRC_9") (pintype "input"))
    )
    (net (code "67") (name "unconnected-(U1-CHG-Pad2)") (class "Default")
      (node (ref "U1") (pin "2") (pinfunction "CHG_2") (pintype "output"))
    )
    (net (code "68") (name "unconnected-(U1-NC-Pad11)") (class "Default")
      (node (ref "U1") (pin "11") (pinfunction "NC_11") (pintype "no_connect"))
    )
    (net (code "69") (name "unconnected-(U2-PG-Pad4)") (class "Default")
      (node (ref "U2") (pin "4") (pinfunction "PG_4") (pintype "open_collector"))
    )
    (net (code "70") (name "unconnected-(U3-(ICP1{slash}ADC8)PD4-Pad25)") (class "Default")
      (node (ref "U3") (pin "25") (pinfunction "(ICP1/ADC8)PD4_25") (pintype "bidirectional"))
    )
  )
)
